# pits_hx1_v1_0.net
KiCad netlist of a schematic drawn in EAGLE
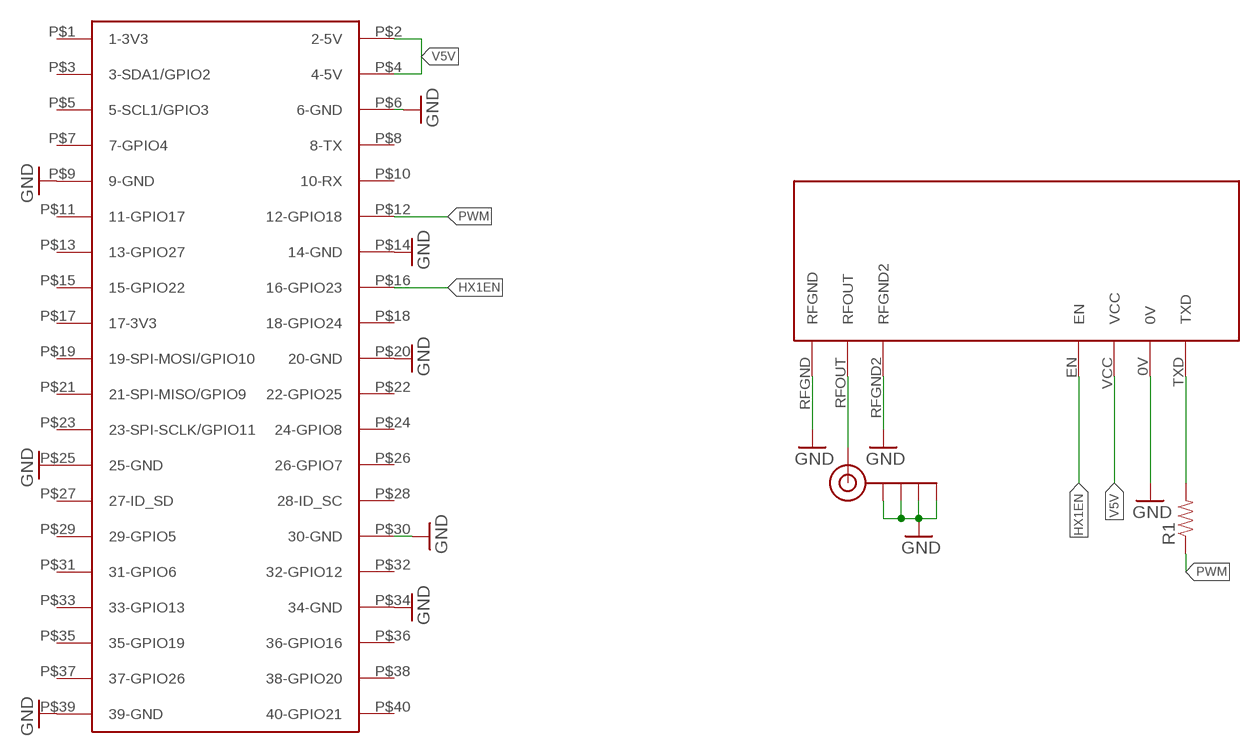
[diagram p0: schematic, sheet 1]

(export (version "E")
  (design (tool "Eeschema 10.0.6"))
  (components
    (comp (ref "J$1")
      (value "SMA_EDGE")
      (footprint "eagle-import:SMA-EDGE")
      (libsource (lib "eagle-import") (part "SMA_EDGE"))
    )
    (comp (ref "R1")
      (value "RESISTOR0603-RES")
      (footprint "eagle-import:0603-RES")
      (libsource (lib "eagle-import") (part "RESISTOR0603-RES"))
    )
    (comp (ref "U$1")
      (value "RASPBERRY-PI+")
      (footprint "eagle-import:RASPBERRY-PI-PLUS-CAM_NOTCH")
      (libsource (lib "eagle-import") (part "RASPBERRY-PI+"))
    )
    (comp (ref "U$2")
      (value "RADIOMETRIX-HX1")
      (footprint "eagle-import:RADIOMETRIX-HX1")
      (libsource (lib "eagle-import") (part "RADIOMETRIX-HX1"))
    )
  )
  (nets
    (net (code "1") (name "GND") (class "Default")
      (node (ref "J$1") (pin "GND@0") (pinfunction "GND_GND@0") (pintype "bidirectional"))
      (node (ref "J$1") (pin "GND@1") (pinfunction "GND_GND@1") (pintype "bidirectional"))
      (node (ref "J$1") (pin "GND@2") (pinfunction "GND_GND@2") (pintype "bidirectional"))
      (node (ref "J$1") (pin "GND@3") (pinfunction "GND_GND@3") (pintype "bidirectional"))
      (node (ref "U$1") (pin "P$14") (pinfunction "14-GND_P$14") (pintype "bidirectional"))
      (node (ref "U$1") (pin "P$20") (pinfunction "20-GND_P$20") (pintype "bidirectional"))
      (node (ref "U$1") (pin "P$25") (pinfunction "25-GND_P$25") (pintype "bidirectional"))
      (node (ref "U$1") (pin "P$30") (pinfunction "30-GND_P$30") (pintype "bidirectional"))
      (node (ref "U$1") (pin "P$34") (pinfunction "34-GND_P$34") (pintype "bidirectional"))
      (node (ref "U$1") (pin "P$39") (pinfunction "39-GND_P$39") (pintype "bidirectional"))
      (node (ref "U$1") (pin "P$6") (pinfunction "6-GND_P$6") (pintype "bidirectional"))
      (node (ref "U$1") (pin "P$9") (pinfunction "9-GND_P$9") (pintype "bidirectional"))
      (node (ref "U$2") (pin "0V") (pinfunction "0V_0V") (pintype "bidirectional"))
      (node (ref "U$2") (pin "RFGND") (pinfunction "RFGND_RFGND") (pintype "bidirectional"))
      (node (ref "U$2") (pin "RFGND2") (pinfunction "RFGND2_RFGND2") (pintype "bidirectional"))
    )
    (net (code "2") (name "HX1EN") (class "Default")
      (node (ref "U$1") (pin "P$16") (pinfunction "16-GPIO23_P$16") (pintype "bidirectional"))
      (node (ref "U$2") (pin "EN") (pinfunction "EN_EN") (pintype "bidirectional"))
    )
    (net (code "3") (name "Net-(J$1-SIGNAL)") (class "Default")
      (node (ref "J$1") (pin "SIG") (pinfunction "SIGNAL_SIG") (pintype "bidirectional"))
      (node (ref "U$2") (pin "RFOUT") (pinfunction "RFOUT_RFOUT") (pintype "bidirectional"))
    )
    (net (code "4") (name "Net-(R1-Pad2)") (class "Default")
      (node (ref "R1") (pin "2") (pinfunction "2_2") (pintype "passive"))
      (node (ref "U$2") (pin "TXD") (pinfunction "TXD_TXD") (pintype "bidirectional"))
    )
    (net (code "5") (name "PWM") (class "Default")
      (node (ref "R1") (pin "1") (pinfunction "1_1") (pintype "passive"))
      (node (ref "U$1") (pin "P$12") (pinfunction "12-GPIO18_P$12") (pintype "bidirectional"))
    )
    (net (code "6") (name "V5V") (class "Default")
      (node (ref "U$1") (pin "P$2") (pinfunction "2-5V_P$2") (pintype "bidirectional"))
      (node (ref "U$1") (pin "P$4") (pinfunction "4-5V_P$4") (pintype "bidirectional"))
      (node (ref "U$2") (pin "VCC") (pinfunction "VCC_VCC") (pintype "bidirectional"))
    )
    (net (code "7") (name "unconnected-(U$1-1-3V3-PadP$1)") (class "Default")
      (node (ref "U$1") (pin "P$1") (pinfunction "1-3V3_P$1") (pintype "bidirectional"))
    )
    (net (code "8") (name "unconnected-(U$1-3-SDA1{slash}GPIO2-PadP$3)") (class "Default")
      (node (ref "U$1") (pin "P$3") (pinfunction "3-SDA1/GPIO2_P$3") (pintype "bidirectional"))
    )
    (net (code "9") (name "unconnected-(U$1-5-SCL1{slash}GPIO3-PadP$5)") (class "Default")
      (node (ref "U$1") (pin "P$5") (pinfunction "5-SCL1/GPIO3_P$5") (pintype "bidirectional"))
    )
    (net (code "10") (name "unconnected-(U$1-7-GPIO4-PadP$7)") (class "Default")
      (node (ref "U$1") (pin "P$7") (pinfunction "7-GPIO4_P$7") (pintype "bidirectional"))
    )
    (net (code "11") (name "unconnected-(U$1-8-TX-PadP$8)") (class "Default")
      (node (ref "U$1") (pin "P$8") (pinfunction "8-TX_P$8") (pintype "bidirectional"))
    )
    (net (code "12") (name "unconnected-(U$1-10-RX-PadP$10)") (class "Default")
      (node (ref "U$1") (pin "P$10") (pinfunction "10-RX_P$10") (pintype "bidirectional"))
    )
    (net (code "13") (name "unconnected-(U$1-11-GPIO17-PadP$11)") (class "Default")
      (node (ref "U$1") (pin "P$11") (pinfunction "11-GPIO17_P$11") (pintype "bidirectional"))
    )
    (net (code "14") (name "unconnected-(U$1-13-GPIO27-PadP$13)") (class "Default")
      (node (ref "U$1") (pin "P$13") (pinfunction "13-GPIO27_P$13") (pintype "bidirectional"))
    )
    (net (code "15") (name "unconnected-(U$1-15-GPIO22-PadP$15)") (class "Default")
      (node (ref "U$1") (pin "P$15") (pinfunction "15-GPIO22_P$15") (pintype "bidirectional"))
    )
    (net (code "16") (name "unconnected-(U$1-17-3V3-PadP$17)") (class "Default")
      (node (ref "U$1") (pin "P$17") (pinfunction "17-3V3_P$17") (pintype "bidirectional"))
    )
    (net (code "17") (name "unconnected-(U$1-18-GPIO24-PadP$18)") (class "Default")
      (node (ref "U$1") (pin "P$18") (pinfunction "18-GPIO24_P$18") (pintype "bidirectional"))
    )
    (net (code "18") (name "unconnected-(U$1-19-SPI-MOSI{slash}GPIO10-PadP$19)") (class "Default")
      (node (ref "U$1") (pin "P$19") (pinfunction "19-SPI-MOSI/GPIO10_P$19") (pintype "bidirectional"))
    )
    (net (code "19") (name "unconnected-(U$1-21-SPI-MISO{slash}GPIO9-PadP$21)") (class "Default")
      (node (ref "U$1") (pin "P$21") (pinfunction "21-SPI-MISO/GPIO9_P$21") (pintype "bidirectional"))
    )
    (net (code "20") (name "unconnected-(U$1-22-GPIO25-PadP$22)") (class "Default")
      (node (ref "U$1") (pin "P$22") (pinfunction "22-GPIO25_P$22") (pintype "bidirectional"))
    )
    (net (code "21") (name "unconnected-(U$1-23-SPI-SCLK{slash}GPIO11-PadP$23)") (class "Default")
      (node (ref "U$1") (pin "P$23") (pinfunction "23-SPI-SCLK/GPIO11_P$23") (pintype "bidirectional"))
    )
    (net (code "22") (name "unconnected-(U$1-24-GPIO8-PadP$24)") (class "Default")
      (node (ref "U$1") (pin "P$24") (pinfunction "24-GPIO8_P$24") (pintype "bidirectional"))
    )
    (net (code "23") (name "unconnected-(U$1-26-GPIO7-PadP$26)") (class "Default")
      (node (ref "U$1") (pin "P$26") (pinfunction "26-GPIO7_P$26") (pintype "bidirectional"))
    )
    (net (code "24") (name "unconnected-(U$1-27-ID_SD-PadP$27)") (class "Default")
      (node (ref "U$1") (pin "P$27") (pinfunction "27-ID_SD_P$27") (pintype "bidirectional"))
    )
    (net (code "25") (name "unconnected-(U$1-28-ID_SC-PadP$28)") (class "Default")
      (node (ref "U$1") (pin "P$28") (pinfunction "28-ID_SC_P$28") (pintype "bidirectional"))
    )
    (net (code "26") (name "unconnected-(U$1-29-GPIO5-PadP$29)") (class "Default")
      (node (ref "U$1") (pin "P$29") (pinfunction "29-GPIO5_P$29") (pintype "bidirectional"))
    )
    (net (code "27") (name "unconnected-(U$1-31-GPIO6-PadP$31)") (class "Default")
      (node (ref "U$1") (pin "P$31") (pinfunction "31-GPIO6_P$31") (pintype "bidirectional"))
    )
    (net (code "28") (name "unconnected-(U$1-32-GPIO12-PadP$32)") (class "Default")
      (node (ref "U$1") (pin "P$32") (pinfunction "32-GPIO12_P$32") (pintype "bidirectional"))
    )
    (net (code "29") (name "unconnected-(U$1-33-GPIO13-PadP$33)") (class "Default")
      (node (ref "U$1") (pin "P$33") (pinfunction "33-GPIO13_P$33") (pintype "bidirectional"))
    )
    (net (code "30") (name "unconnected-(U$1-35-GPIO19-PadP$35)") (class "Default")
      (node (ref "U$1") (pin "P$35") (pinfunction "35-GPIO19_P$35") (pintype "bidirectional"))
    )
    (net (code "31") (name "unconnected-(U$1-36-GPIO16-PadP$36)") (class "Default")
      (node (ref "U$1") (pin "P$36") (pinfunction "36-GPIO16_P$36") (pintype "bidirectional"))
    )
    (net (code "32") (name "unconnected-(U$1-37-GPIO26-PadP$37)") (class "Default")
      (node (ref "U$1") (pin "P$37") (pinfunction "37-GPIO26_P$37") (pintype "bidirectional"))
    )
    (net (code "33") (name "unconnected-(U$1-38-GPIO20-PadP$38)") (class "Default")
      (node (ref "U$1") (pin "P$38") (pinfunction "38-GPIO20_P$38") (pintype "bidirectional"))
    )
    (net (code "34") (name "unconnected-(U$1-40-GPIO21-PadP$40)") (class "Default")
      (node (ref "U$1") (pin "P$40") (pinfunction "40-GPIO21_P$40") (pintype "bidirectional"))
    )
  )
)
